# Adafruit_ATtiny8x7_Breakout.net
KiCad netlist of a schematic drawn in EAGLE
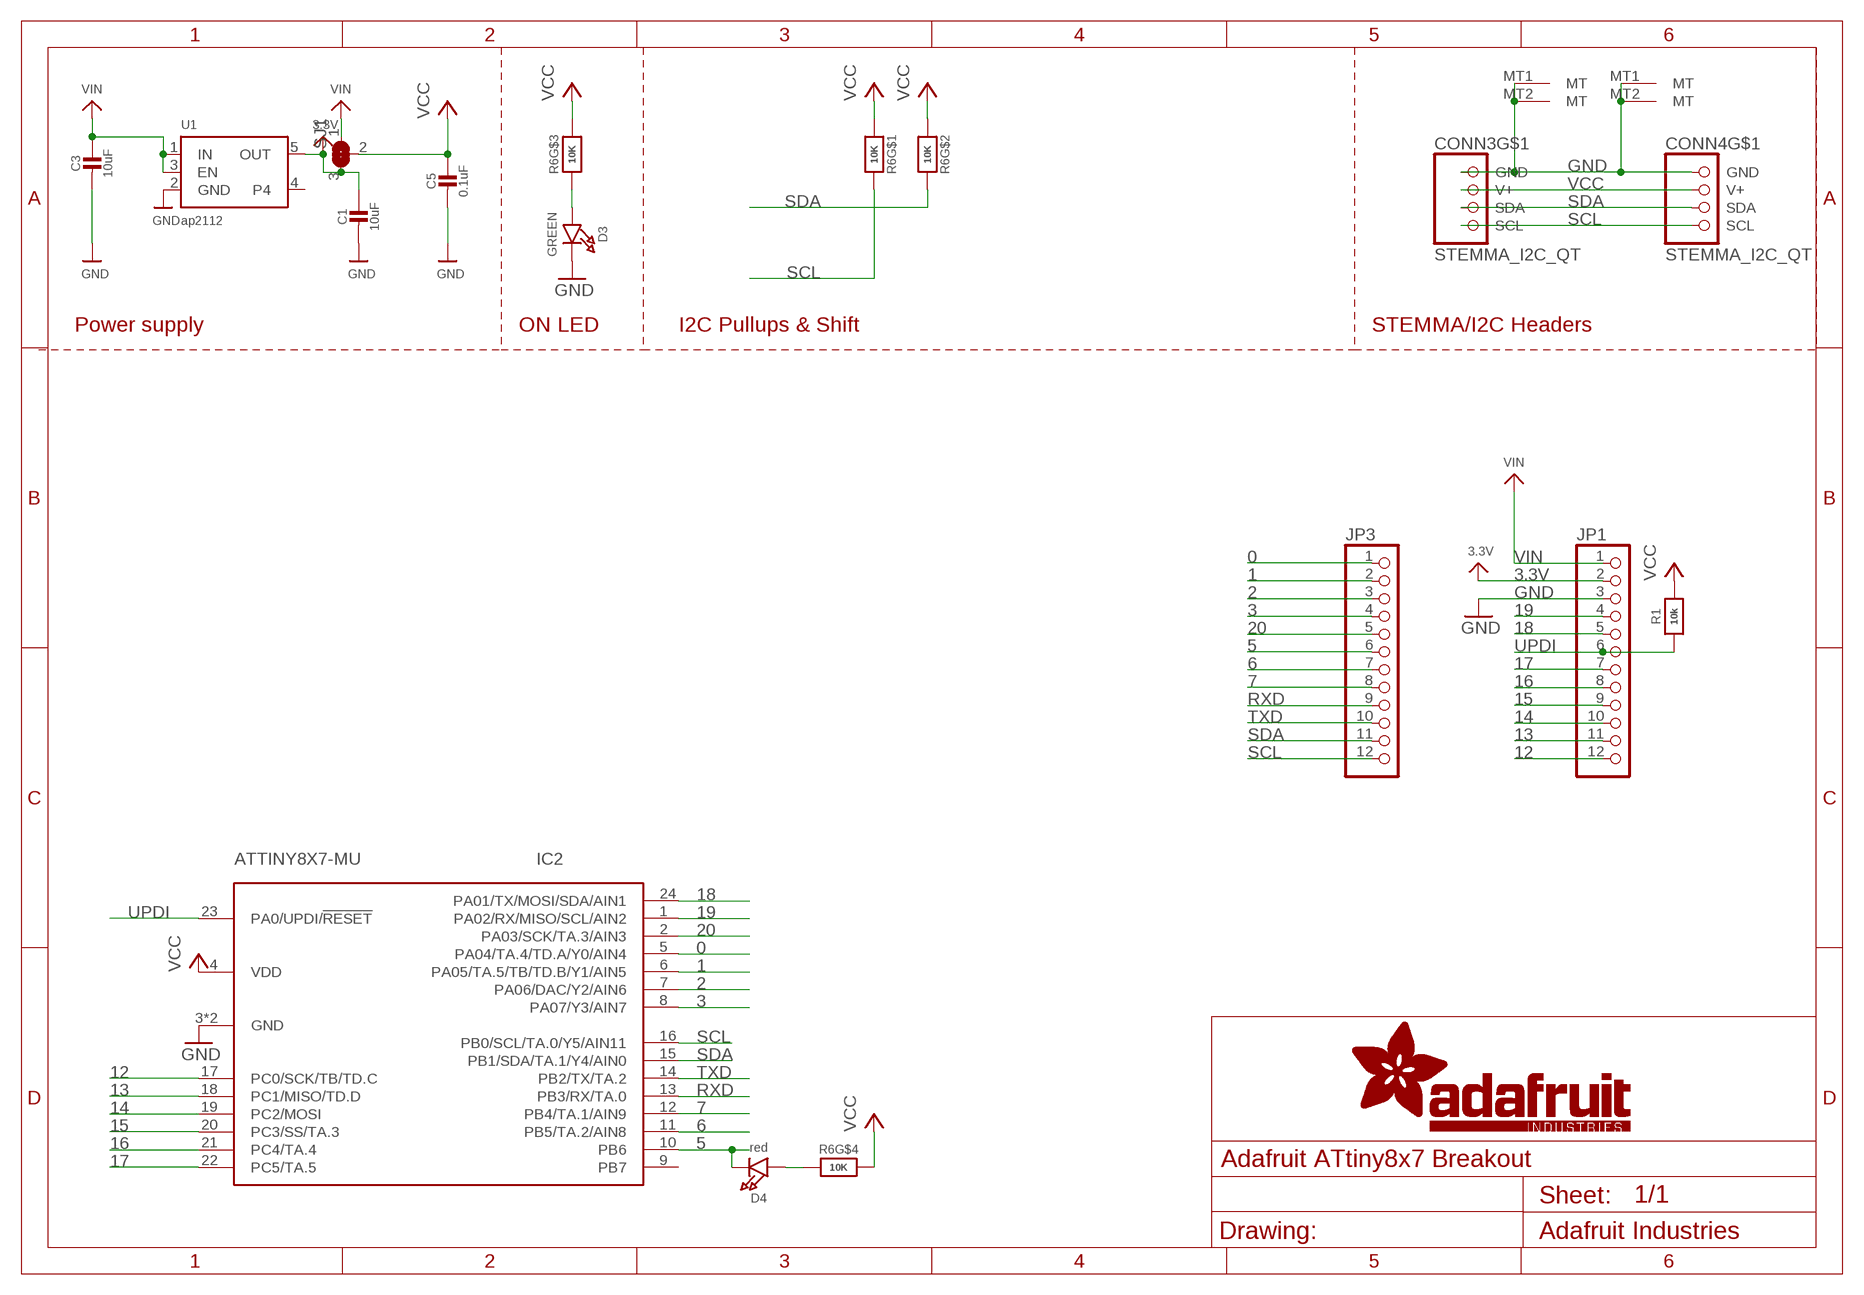
[diagram p0: schematic, sheet 1]

(export (version "E")
  (design (tool "Eeschema 10.0.6"))
  (components
    (comp (ref "C1")
      (value "10uF")
      (footprint "eagle-import:0805_10MGAP")
      (libsource (lib "eagle-import") (part "CAP_CERAMIC0805_10MGAP"))
    )
    (comp (ref "C3")
      (value "10uF")
      (footprint "eagle-import:0805-NO")
      (libsource (lib "eagle-import") (part "CAP_CERAMIC0805-NOOUTLINE"))
    )
    (comp (ref "C5")
      (value "0.1uF")
      (footprint "eagle-import:0603-NO")
      (libsource (lib "eagle-import") (part "CAP_CERAMIC0603_NO"))
    )
    (comp (ref "CONN3")
      (value "STEMMA_I2C_QT")
      (footprint "eagle-import:JST_SH4")
      (libsource (lib "eagle-import") (part "STEMMA_I2C_QT"))
    )
    (comp (ref "CONN4")
      (value "STEMMA_I2C_QT")
      (footprint "eagle-import:JST_SH4")
      (libsource (lib "eagle-import") (part "STEMMA_I2C_QT"))
    )
    (comp (ref "D3")
      (value "GREEN")
      (footprint "eagle-import:CHIPLED_0603_NOOUTLINE")
      (libsource (lib "eagle-import") (part "LED0603_NOOUTLINE"))
    )
    (comp (ref "D4")
      (value "red")
      (footprint "eagle-import:CHIPLED_0603_NOOUTLINE")
      (libsource (lib "eagle-import") (part "LED0603_NOOUTLINE"))
    )
    (comp (ref "IC2")
      (value "ATTINY8X7-MU")
      (footprint "eagle-import:QFN24_4MM")
      (libsource (lib "eagle-import") (part "ATTINY8X7-MU"))
    )
    (comp (ref "JP1")
      (value "HEADER-1X1276MIL")
      (footprint "eagle-import:1X12_ROUND_76MIL")
      (libsource (lib "eagle-import") (part "HEADER-1X1276MIL"))
    )
    (comp (ref "JP3")
      (value "HEADER-1X1276MIL")
      (footprint "eagle-import:1X12_ROUND_76MIL")
      (libsource (lib "eagle-import") (part "HEADER-1X1276MIL"))
    )
    (comp (ref "R1")
      (value "10k")
      (footprint "eagle-import:0603-NO")
      (libsource (lib "eagle-import") (part "RESISTOR_0603_NOOUT"))
    )
    (comp (ref "R6")
      (value "10K")
      (footprint "eagle-import:RESPACK_4X0603")
      (libsource (lib "eagle-import") (part "RESISTOR_4PACK"))
    )
    (comp (ref "SJ1")
      (value "SOLDERJUMPER_2WAY")
      (footprint "eagle-import:SOLDERJUMPER_2WAY_OPEN_NOPASTE")
      (libsource (lib "eagle-import") (part "SOLDERJUMPER_2WAY"))
    )
    (comp (ref "U1")
      (value "ap2112")
      (footprint "eagle-import:SOT23-5")
      (libsource (lib "eagle-import") (part "VREG_SOT23-5"))
    )
  )
  (nets
    (net (code "1") (name "/0") (class "Default")
      (node (ref "IC2") (pin "5") (pinfunction "PA04/TA.4/TD.A/Y0/AIN4_5") (pintype "bidirectional"))
      (node (ref "JP3") (pin "1") (pinfunction "1_1") (pintype "passive"))
    )
    (net (code "2") (name "/1") (class "Default")
      (node (ref "IC2") (pin "6") (pinfunction "PA05/TA.5/TB/TD.B/Y1/AIN5_6") (pintype "bidirectional"))
      (node (ref "JP3") (pin "2") (pinfunction "2_2") (pintype "passive"))
    )
    (net (code "3") (name "/2") (class "Default")
      (node (ref "IC2") (pin "7") (pinfunction "PA06/DAC/Y2/AIN6_7") (pintype "bidirectional"))
      (node (ref "JP3") (pin "3") (pinfunction "3_3") (pintype "passive"))
    )
    (net (code "4") (name "/3") (class "Default")
      (node (ref "IC2") (pin "8") (pinfunction "PA07/Y3/AIN7_8") (pintype "bidirectional"))
      (node (ref "JP3") (pin "4") (pinfunction "4_4") (pintype "passive"))
    )
    (net (code "5") (name "/5") (class "Default")
      (node (ref "D4") (pin "C") (pinfunction "C_C") (pintype "passive"))
      (node (ref "IC2") (pin "10") (pinfunction "PB6_10") (pintype "bidirectional"))
      (node (ref "JP3") (pin "6") (pinfunction "6_6") (pintype "passive"))
    )
    (net (code "6") (name "/6") (class "Default")
      (node (ref "IC2") (pin "11") (pinfunction "PB5/TA.2/AIN8_11") (pintype "bidirectional"))
      (node (ref "JP3") (pin "7") (pinfunction "7_7") (pintype "passive"))
    )
    (net (code "7") (name "/7") (class "Default")
      (node (ref "IC2") (pin "12") (pinfunction "PB4/TA.1/AIN9_12") (pintype "bidirectional"))
      (node (ref "JP3") (pin "8") (pinfunction "8_8") (pintype "passive"))
    )
    (net (code "8") (name "/12") (class "Default")
      (node (ref "IC2") (pin "17") (pinfunction "PC0/SCK/TB/TD.C_17") (pintype "bidirectional"))
      (node (ref "JP1") (pin "12") (pinfunction "12_12") (pintype "passive"))
    )
    (net (code "9") (name "/13") (class "Default")
      (node (ref "IC2") (pin "18") (pinfunction "PC1/MISO/TD.D_18") (pintype "bidirectional"))
      (node (ref "JP1") (pin "11") (pinfunction "11_11") (pintype "passive"))
    )
    (net (code "10") (name "/14") (class "Default")
      (node (ref "IC2") (pin "19") (pinfunction "PC2/MOSI_19") (pintype "bidirectional"))
      (node (ref "JP1") (pin "10") (pinfunction "10_10") (pintype "passive"))
    )
    (net (code "11") (name "/15") (class "Default")
      (node (ref "IC2") (pin "20") (pinfunction "PC3/SS/TA.3_20") (pintype "bidirectional"))
      (node (ref "JP1") (pin "9") (pinfunction "9_9") (pintype "passive"))
    )
    (net (code "12") (name "/16") (class "Default")
      (node (ref "IC2") (pin "21") (pinfunction "PC4/TA.4_21") (pintype "bidirectional"))
      (node (ref "JP1") (pin "8") (pinfunction "8_8") (pintype "passive"))
    )
    (net (code "13") (name "/17") (class "Default")
      (node (ref "IC2") (pin "22") (pinfunction "PC5/TA.5_22") (pintype "bidirectional"))
      (node (ref "JP1") (pin "7") (pinfunction "7_7") (pintype "passive"))
    )
    (net (code "14") (name "/18") (class "Default")
      (node (ref "IC2") (pin "24") (pinfunction "PA01/TX/MOSI/SDA/AIN1_24") (pintype "bidirectional"))
      (node (ref "JP1") (pin "5") (pinfunction "5_5") (pintype "passive"))
    )
    (net (code "15") (name "/19") (class "Default")
      (node (ref "IC2") (pin "1") (pinfunction "PA02/RX/MISO/SCL/AIN2_1") (pintype "bidirectional"))
      (node (ref "JP1") (pin "4") (pinfunction "4_4") (pintype "passive"))
    )
    (net (code "16") (name "/20") (class "Default")
      (node (ref "IC2") (pin "2") (pinfunction "PA03/SCK/TA.3/AIN3_2") (pintype "bidirectional"))
      (node (ref "JP3") (pin "5") (pinfunction "5_5") (pintype "passive"))
    )
    (net (code "17") (name "/RXD") (class "Default")
      (node (ref "IC2") (pin "13") (pinfunction "PB3/RX/TA.0_13") (pintype "bidirectional"))
      (node (ref "JP3") (pin "9") (pinfunction "9_9") (pintype "passive"))
    )
    (net (code "18") (name "/SCL") (class "Default")
      (node (ref "CONN3") (pin "4") (pinfunction "SCL_4") (pintype "passive"))
      (node (ref "CONN4") (pin "4") (pinfunction "SCL_4") (pintype "passive"))
      (node (ref "IC2") (pin "16") (pinfunction "PB0/SCL/TA.0/Y5/AIN11_16") (pintype "bidirectional"))
      (node (ref "JP3") (pin "12") (pinfunction "12_12") (pintype "passive"))
      (node (ref "R6") (pin "8") (pinfunction "2_8") (pintype "passive"))
    )
    (net (code "19") (name "/SDA") (class "Default")
      (node (ref "CONN3") (pin "3") (pinfunction "SDA_3") (pintype "passive"))
      (node (ref "CONN4") (pin "3") (pinfunction "SDA_3") (pintype "passive"))
      (node (ref "IC2") (pin "15") (pinfunction "PB1/SDA/TA.1/Y4/AIN0_15") (pintype "bidirectional"))
      (node (ref "JP3") (pin "11") (pinfunction "11_11") (pintype "passive"))
      (node (ref "R6") (pin "7") (pinfunction "2_7") (pintype "passive"))
    )
    (net (code "20") (name "/TXD") (class "Default")
      (node (ref "IC2") (pin "14") (pinfunction "PB2/TX/TA.2_14") (pintype "bidirectional"))
      (node (ref "JP3") (pin "10") (pinfunction "10_10") (pintype "passive"))
    )
    (net (code "21") (name "/UPDI") (class "Default")
      (node (ref "IC2") (pin "23") (pinfunction "PA0/UPDI/~{RESET}_23") (pintype "bidirectional"))
      (node (ref "JP1") (pin "6") (pinfunction "6_6") (pintype "passive"))
      (node (ref "R1") (pin "1") (pinfunction "1_1") (pintype "passive"))
    )
    (net (code "22") (name "3.3V") (class "Default")
      (node (ref "C1") (pin "1") (pinfunction "1_1") (pintype "passive"))
      (node (ref "JP1") (pin "2") (pinfunction "2_2") (pintype "passive"))
      (node (ref "SJ1") (pin "3") (pinfunction "3_3") (pintype "passive"))
      (node (ref "U1") (pin "5") (pinfunction "OUT_5") (pintype "power_in"))
    )
    (net (code "23") (name "GND") (class "Default")
      (node (ref "C1") (pin "2") (pinfunction "2_2") (pintype "passive"))
      (node (ref "C3") (pin "2") (pinfunction "2_2") (pintype "passive"))
      (node (ref "C5") (pin "2") (pinfunction "2_2") (pintype "passive"))
      (node (ref "CONN3") (pin "1") (pinfunction "GND_1") (pintype "passive"))
      (node (ref "CONN3") (pin "MT1") (pinfunction "MT_MT1") (pintype "bidirectional"))
      (node (ref "CONN3") (pin "MT2") (pinfunction "MT_MT2") (pintype "bidirectional"))
      (node (ref "CONN4") (pin "1") (pinfunction "GND_1") (pintype "passive"))
      (node (ref "CONN4") (pin "MT1") (pinfunction "MT_MT1") (pintype "bidirectional"))
      (node (ref "CONN4") (pin "MT2") (pinfunction "MT_MT2") (pintype "bidirectional"))
      (node (ref "D3") (pin "C") (pinfunction "C_C") (pintype "passive"))
      (node (ref "IC2") (pin "3") (pinfunction "GND_3") (pintype "power_in"))
      (node (ref "IC2") (pin "THERM") (pinfunction "GND_THERM") (pintype "power_in"))
      (node (ref "JP1") (pin "3") (pinfunction "3_3") (pintype "passive"))
      (node (ref "U1") (pin "2") (pinfunction "GND_2") (pintype "power_in"))
    )
    (net (code "24") (name "Net-(R6C-1)") (class "Default")
      (node (ref "D3") (pin "A") (pinfunction "A_A") (pintype "passive"))
      (node (ref "R6") (pin "3") (pinfunction "1_3") (pintype "passive"))
    )
    (net (code "25") (name "Net-(R6D-1)") (class "Default")
      (node (ref "D4") (pin "A") (pinfunction "A_A") (pintype "passive"))
      (node (ref "R6") (pin "4") (pinfunction "1_4") (pintype "passive"))
    )
    (net (code "26") (name "VCC") (class "Default")
      (node (ref "C5") (pin "1") (pinfunction "1_1") (pintype "passive"))
      (node (ref "CONN3") (pin "2") (pinfunction "V+_2") (pintype "passive"))
      (node (ref "CONN4") (pin "2") (pinfunction "V+_2") (pintype "passive"))
      (node (ref "IC2") (pin "4") (pinfunction "VDD_4") (pintype "power_in"))
      (node (ref "R1") (pin "2") (pinfunction "2_2") (pintype "passive"))
      (node (ref "R6") (pin "1") (pinfunction "1_1") (pintype "passive"))
      (node (ref "R6") (pin "2") (pinfunction "1_2") (pintype "passive"))
      (node (ref "R6") (pin "5") (pinfunction "2_5") (pintype "passive"))
      (node (ref "R6") (pin "6") (pinfunction "2_6") (pintype "passive"))
      (node (ref "SJ1") (pin "2") (pinfunction "2_2") (pintype "passive"))
    )
    (net (code "27") (name "VIN") (class "Default")
      (node (ref "C3") (pin "1") (pinfunction "1_1") (pintype "passive"))
      (node (ref "JP1") (pin "1") (pinfunction "1_1") (pintype "passive"))
      (node (ref "SJ1") (pin "1") (pinfunction "1_1") (pintype "passive"))
      (node (ref "U1") (pin "1") (pinfunction "IN_1") (pintype "power_in"))
      (node (ref "U1") (pin "3") (pinfunction "EN_3") (pintype "input"))
    )
    (net (code "28") (name "unconnected-(IC2-PB7-Pad9)") (class "Default")
      (node (ref "IC2") (pin "9") (pinfunction "PB7_9") (pintype "bidirectional"))
    )
    (net (code "29") (name "unconnected-(U1-P4-Pad4)") (class "Default")
      (node (ref "U1") (pin "4") (pinfunction "P4_4") (pintype "bidirectional"))
    )
  )
)
